# Main_Pannel_ATMega328p_2020-08-23_19-58-.net
KiCad netlist of a schematic drawn in EasyEDA
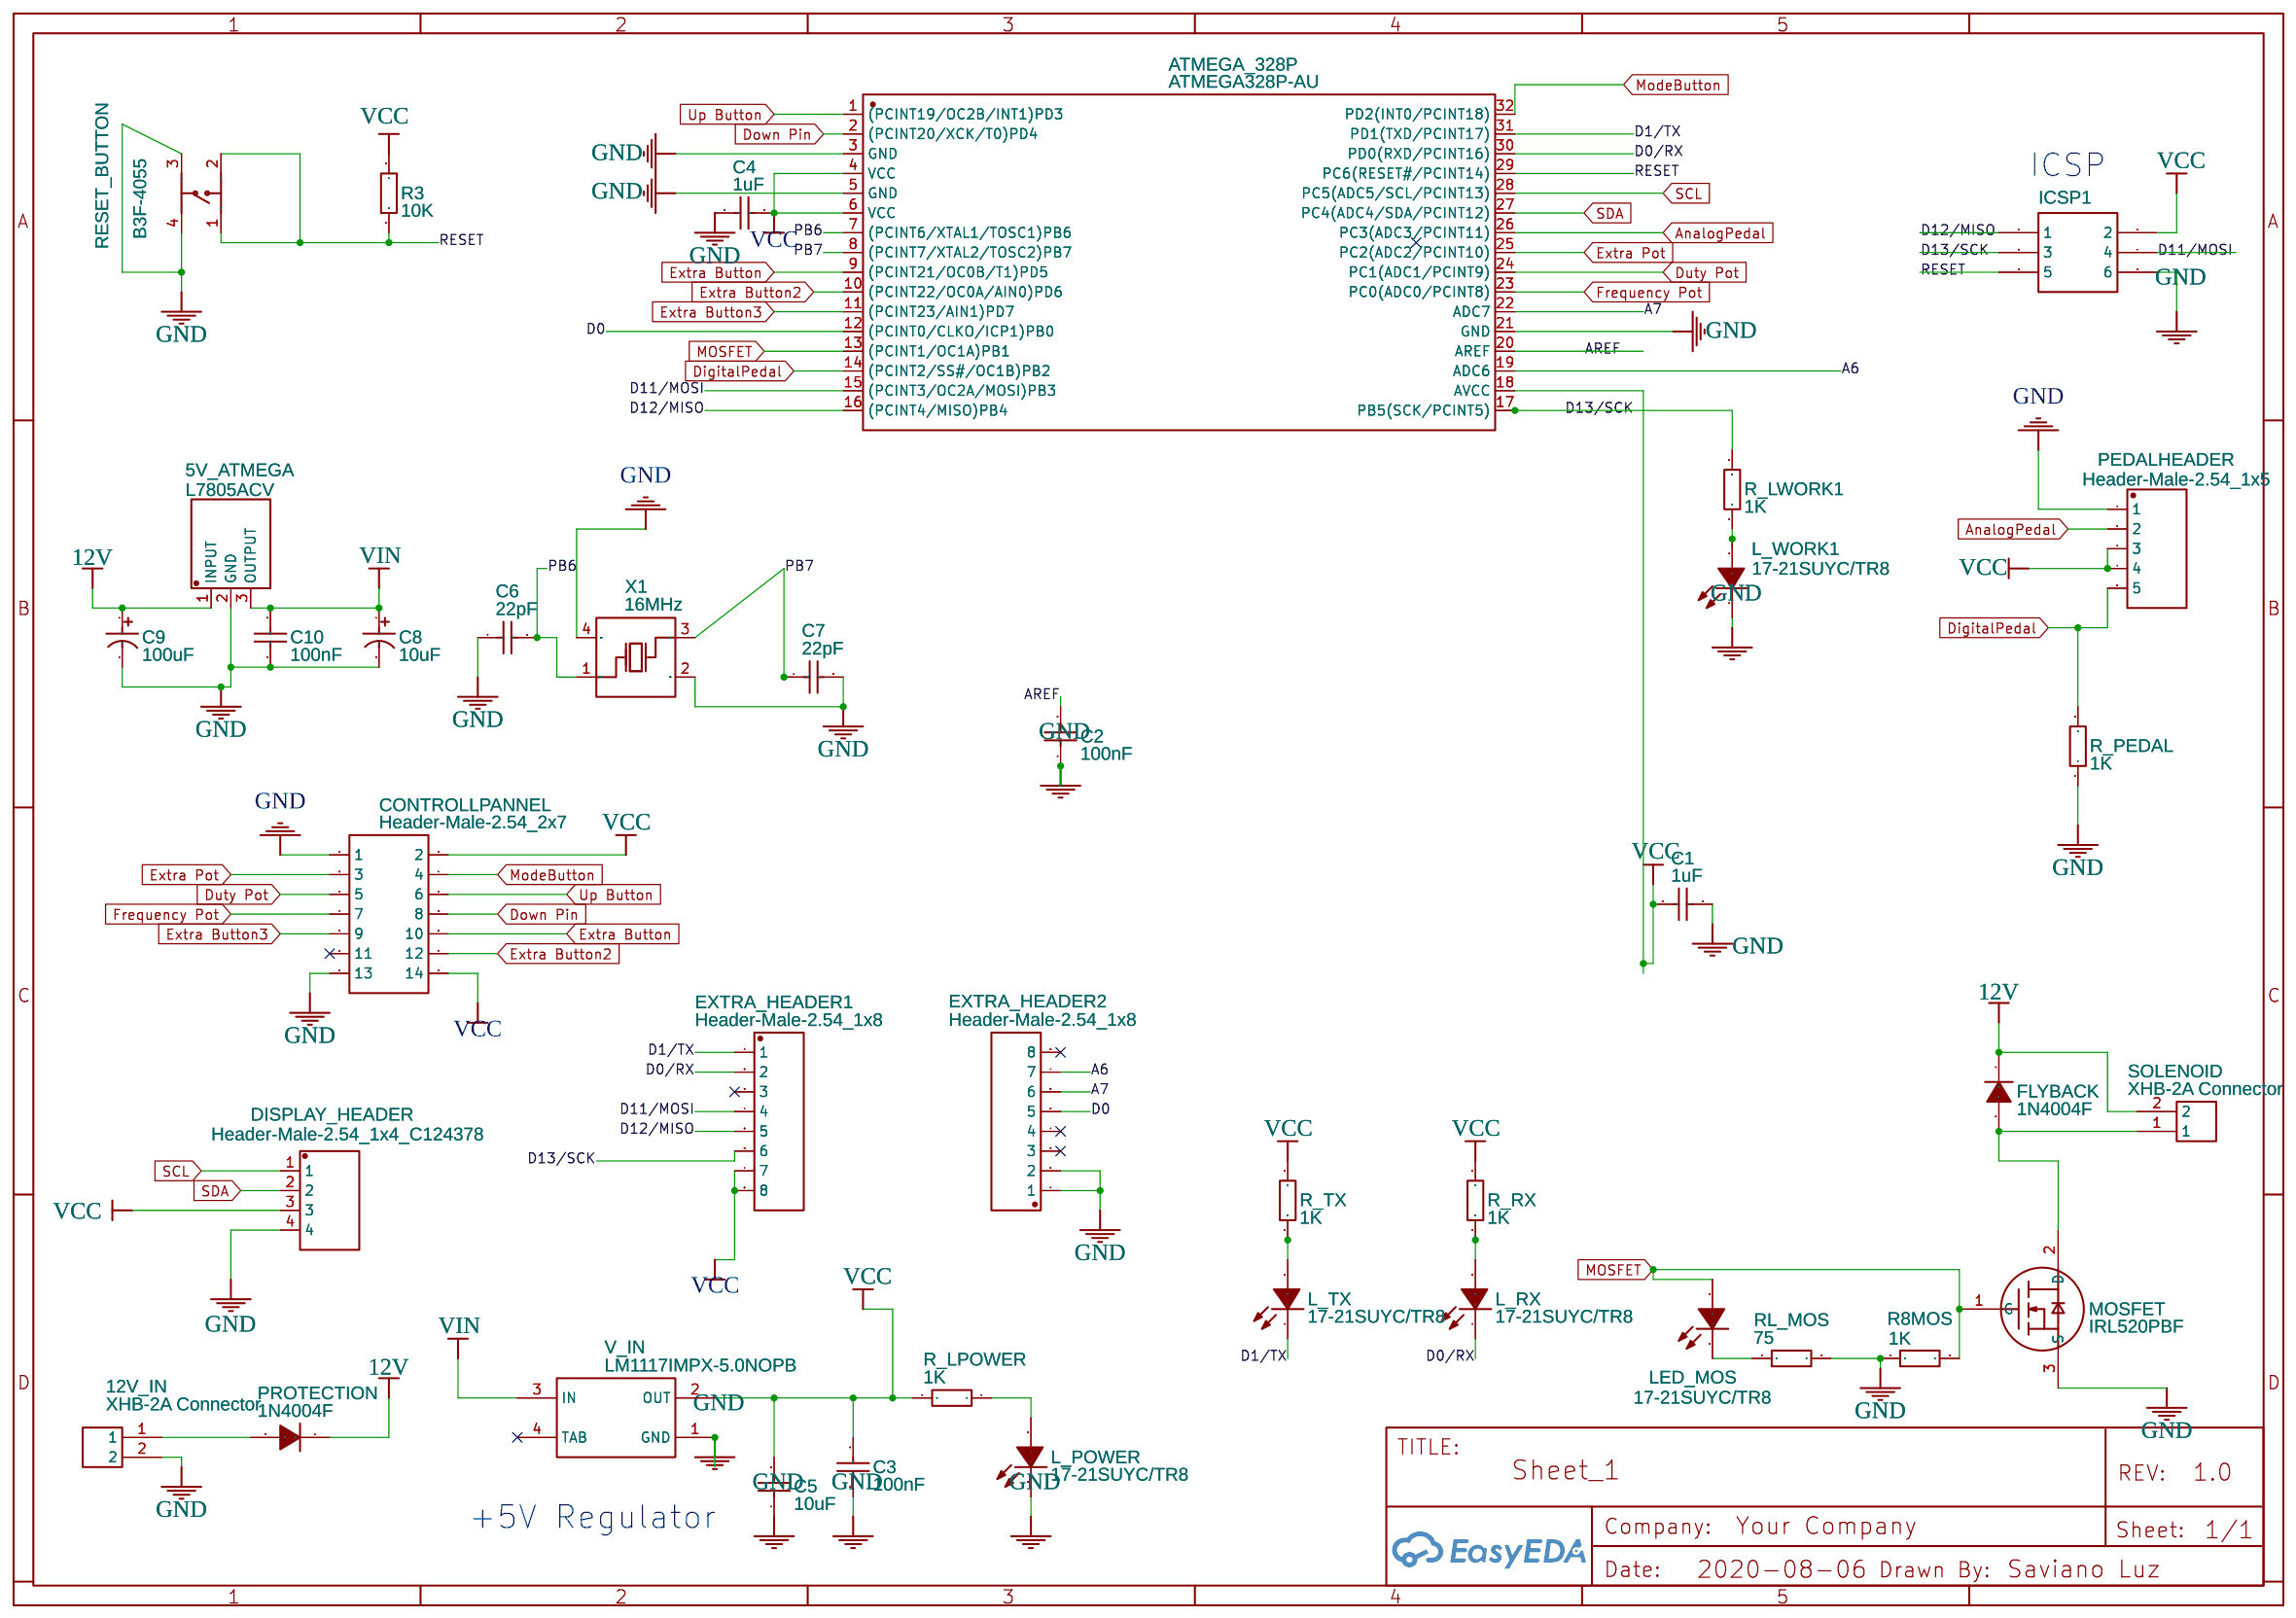
[diagram p0: schematic sheet]

(export (version "E")
  (design (tool "Eeschema 10.0.6"))
  (components
    (comp (ref "5V_ATMEGA")
      (value "L7805ACV")
      (fields (field (name "BOM_Supplier Part") "C192854"))
      (libsource (lib "") (part "L7805ACV"))
    )
    (comp (ref "12V_IN")
      (value "XHB-2A Connector")
      (fields (field (name "BOM_Supplier Part") "C57981"))
      (libsource (lib "") (part "XHB-2A Connector"))
    )
    (comp (ref "ATMEGA_328P")
      (value "ATMEGA328P-AU")
      (fields (field (name "BOM_Supplier Part") "C14877"))
      (libsource (lib "") (part "ATMEGA328P-AU"))
    )
    (comp (ref "C1")
      (value "1uF")
      (fields
        (field (name "BOM_Manufacturer Part") "CL10A105KB8NNNC")
        (field (name "BOM_Supplier Part") "C15849")
      )
      (libsource (lib "") (part "CL10A105KB8NNNC"))
    )
    (comp (ref "C2")
      (value "100nF")
      (fields
        (field (name "BOM_Manufacturer Part") "CL31B104KBCNNNC")
        (field (name "BOM_Supplier Part") "C24497")
      )
      (libsource (lib "") (part "CL31B104KBCNNNC"))
    )
    (comp (ref "C3")
      (value "100nF")
      (fields
        (field (name "BOM_Manufacturer Part") "CL31B104KBCNNNC")
        (field (name "BOM_Supplier Part") "C24497")
      )
      (libsource (lib "") (part "CL31B104KBCNNNC"))
    )
    (comp (ref "C4")
      (value "1uF")
      (fields
        (field (name "BOM_Manufacturer Part") "CL10A105KB8NNNC")
        (field (name "BOM_Supplier Part") "C15849")
      )
      (libsource (lib "") (part "CL10A105KB8NNNC"))
    )
    (comp (ref "C5")
      (value "10uF")
      (fields
        (field (name "BOM_Manufacturer Part") "CL31A106KBHNNNE")
        (field (name "BOM_Supplier Part") "C13585")
      )
      (libsource (lib "") (part "CL31A106KBHNNNE"))
    )
    (comp (ref "C6")
      (value "22pF")
      (fields
        (field (name "BOM_Manufacturer Part") "CL21C220JBANNNC")
        (field (name "BOM_Supplier Part") "C1804")
      )
      (libsource (lib "") (part "CL21C220JBANNNC"))
    )
    (comp (ref "C7")
      (value "22pF")
      (fields
        (field (name "BOM_Manufacturer Part") "CL21C220JBANNNC")
        (field (name "BOM_Supplier Part") "C1804")
      )
      (libsource (lib "") (part "CL21C220JBANNNC"))
    )
    (comp (ref "C8")
      (value "10uF")
      (fields
        (field (name "BOM_Manufacturer Part") "C10uF63V2.5mm5x11mm")
        (field (name "BOM_Supplier Part") "C32455")
      )
      (libsource (lib "") (part "C10uF63V2.5mm5x11mm"))
    )
    (comp (ref "C9")
      (value "100uF")
      (fields
        (field (name "BOM_Manufacturer Part") "10X17 100V100uf")
        (field (name "BOM_Supplier Part") "C3336")
      )
      (libsource (lib "") (part "10X17 100V100uf"))
    )
    (comp (ref "C10")
      (value "100nF")
      (fields
        (field (name "BOM_Manufacturer Part") "CL31B104KBCNNNC")
        (field (name "BOM_Supplier Part") "C24497")
      )
      (libsource (lib "") (part "CL31B104KBCNNNC"))
    )
    (comp (ref "CONTROLLPANNEL")
      (value "Header-Male-2.54_2x7")
      (fields
        (field (name "BOM_Manufacturer Part") "Double row of needle2X7P 2.54mm")
        (field (name "BOM_Supplier Part") "C71397")
      )
      (libsource (lib "") (part "Header-Male-2.54_2x7"))
    )
    (comp (ref "DISPLAY_HEADER")
      (value "Header-Male-2.54_1x4_C124378")
      (fields
        (field (name "BOM_Manufacturer Part") "210S-1*4P L=11.6MMGold-plated black")
        (field (name "BOM_Supplier Part") "C124378")
      )
      (libsource (lib "") (part "Header-Male-2.54_1x4_C124378"))
    )
    (comp (ref "EXTRA_HEADER1")
      (value "Header-Male-2.54_1x8")
      (fields
        (field (name "BOM_Manufacturer Part") "210S-1*8P L=11.6MMGold-plated black")
        (field (name "BOM_Supplier Part") "C124381")
      )
      (libsource (lib "") (part "Header-Male-2.54_1x8"))
    )
    (comp (ref "EXTRA_HEADER2")
      (value "Header-Male-2.54_1x8")
      (fields
        (field (name "BOM_Manufacturer Part") "210S-1*8P L=11.6MMGold-plated black")
        (field (name "BOM_Supplier Part") "C124381")
      )
      (libsource (lib "") (part "Header-Male-2.54_1x8_1"))
    )
    (comp (ref "FLYBACK")
      (value "1N4004F")
      (fields (field (name "BOM_Supplier Part") "C122842"))
      (libsource (lib "") (part "1N4004F"))
    )
    (comp (ref "ICSP1")
      (value "HDR2X3")
      (fields (field (name "BOM_Manufacturer Part") "?"))
      (libsource (lib "") (part "Unknown_1045_-685"))
    )
    (comp (ref "LED_MOS")
      (value "17-21SUYC/TR8")
      (fields (field (name "BOM_Supplier Part") "C2296"))
      (libsource (lib "") (part "17-21SUYC/TR8_1"))
    )
    (comp (ref "L_POWER")
      (value "17-21SUYC/TR8")
      (fields (field (name "BOM_Supplier Part") "C2296"))
      (libsource (lib "") (part "17-21SUYC/TR8_2"))
    )
    (comp (ref "L_RX")
      (value "17-21SUYC/TR8")
      (fields (field (name "BOM_Supplier Part") "C2296"))
      (libsource (lib "") (part "17-21SUYC/TR8_3"))
    )
    (comp (ref "L_TX")
      (value "17-21SUYC/TR8")
      (fields (field (name "BOM_Supplier Part") "C2296"))
      (libsource (lib "") (part "17-21SUYC/TR8"))
    )
    (comp (ref "L_WORK1")
      (value "17-21SUYC/TR8")
      (fields (field (name "BOM_Supplier Part") "C2296"))
      (libsource (lib "") (part "17-21SUYC/TR8_4"))
    )
    (comp (ref "MOSFET")
      (value "IRL520PBF")
      (fields (field (name "BOM_Supplier Part") "C145199"))
      (libsource (lib "") (part "IRL520PBF"))
    )
    (comp (ref "PEDALHEADER")
      (value "Header-Male-2.54_1x5")
      (fields
        (field (name "BOM_Manufacturer Part") "210S-1*5P L=11.6MMGold-plated black")
        (field (name "BOM_Supplier Part") "C124379")
      )
      (libsource (lib "") (part "Header-Male-2.54_1x5"))
    )
    (comp (ref "PROTECTION")
      (value "1N4004F")
      (fields (field (name "BOM_Supplier Part") "C122842"))
      (libsource (lib "") (part "1N4004F_1"))
    )
    (comp (ref "R3")
      (value "10K")
      (fields
        (field (name "BOM_Manufacturer Part") "0805W8F1002T5E")
        (field (name "BOM_Supplier Part") "C17414")
      )
      (libsource (lib "") (part "0805W8F1002T5E"))
    )
    (comp (ref "R8MOS")
      (value "1K")
      (fields
        (field (name "BOM_Manufacturer Part") "1206W4F1001T5E")
        (field (name "BOM_Supplier Part") "C4410")
      )
      (libsource (lib "") (part "1206W4F1001T5E"))
    )
    (comp (ref "RESET_BUTTON")
      (value "B3F-4055")
      (fields (field (name "BOM_Supplier Part") "C84931"))
      (libsource (lib "") (part "B3F-4055"))
    )
    (comp (ref "RL_MOS")
      (value "75")
      (fields
        (field (name "BOM_Manufacturer Part") "0805W8F750JT5E")
        (field (name "BOM_Supplier Part") "C20638")
      )
      (libsource (lib "") (part "0805W8F750JT5E"))
    )
    (comp (ref "R_LPOWER")
      (value "1K")
      (fields
        (field (name "BOM_Manufacturer Part") "0805W8F1001T5E")
        (field (name "BOM_Supplier Part") "C17513")
      )
      (libsource (lib "") (part "0805W8F1001T5E_2"))
    )
    (comp (ref "R_LWORK1")
      (value "1K")
      (fields
        (field (name "BOM_Manufacturer Part") "0805W8F1001T5E")
        (field (name "BOM_Supplier Part") "C17513")
      )
      (libsource (lib "") (part "0805W8F1001T5E_4"))
    )
    (comp (ref "R_PEDAL")
      (value "1K")
      (fields
        (field (name "BOM_Manufacturer Part") "0805W8F1001T5E")
        (field (name "BOM_Supplier Part") "C17513")
      )
      (libsource (lib "") (part "0805W8F1001T5E"))
    )
    (comp (ref "R_RX")
      (value "1K")
      (fields
        (field (name "BOM_Manufacturer Part") "0805W8F1001T5E")
        (field (name "BOM_Supplier Part") "C17513")
      )
      (libsource (lib "") (part "0805W8F1001T5E_1"))
    )
    (comp (ref "R_TX")
      (value "1K")
      (fields
        (field (name "BOM_Manufacturer Part") "0805W8F1001T5E")
        (field (name "BOM_Supplier Part") "C17513")
      )
      (libsource (lib "") (part "0805W8F1001T5E_3"))
    )
    (comp (ref "SOLENOID")
      (value "XHB-2A Connector")
      (fields (field (name "BOM_Supplier Part") "C57981"))
      (libsource (lib "") (part "XHB-2A Connector_1"))
    )
    (comp (ref "V_IN")
      (value "LM1117IMPX-5.0NOPB")
      (fields (field (name "BOM_Manufacturer Part") "?") (field (name "BOM_Supplier Part") "C41202"))
      (libsource (lib "") (part "Unknown_305_-95"))
    )
    (comp (ref "X1")
      (value "16MHz")
      (fields
        (field (name "BOM_Manufacturer Part") "X322516MLB4SI")
        (field (name "BOM_Supplier Part") "C13738")
      )
      (libsource (lib "") (part "X322516MLB4SI"))
    )
  )
  (nets
    (net (code "1") (name "/A6") (class "Default")
      (node (ref "ATMEGA_328P") (pin "19") (pinfunction "ADC6_19") (pintype "unspecified"))
      (node (ref "EXTRA_HEADER2") (pin "7") (pinfunction "7_7") (pintype "unspecified"))
    )
    (net (code "2") (name "/A7") (class "Default")
      (node (ref "ATMEGA_328P") (pin "22") (pinfunction "ADC7_22") (pintype "unspecified"))
      (node (ref "EXTRA_HEADER2") (pin "6") (pinfunction "6_6") (pintype "unspecified"))
    )
    (net (code "3") (name "/AREF") (class "Default")
      (node (ref "ATMEGA_328P") (pin "20") (pinfunction "AREF_20") (pintype "unspecified"))
      (node (ref "C2") (pin "2") (pinfunction "2_2") (pintype "input"))
    )
    (net (code "4") (name "/D0") (class "Default")
      (node (ref "ATMEGA_328P") (pin "12") (pinfunction "(PCINT0/CLKO/ICP1)PB0_12") (pintype "unspecified"))
      (node (ref "EXTRA_HEADER2") (pin "5") (pinfunction "5_5") (pintype "unspecified"))
    )
    (net (code "5") (name "/D0{slash}RX") (class "Default")
      (node (ref "ATMEGA_328P") (pin "30") (pinfunction "PD0(RXD/PCINT16)_30") (pintype "unspecified"))
      (node (ref "EXTRA_HEADER1") (pin "2") (pinfunction "2_2") (pintype "unspecified"))
      (node (ref "L_RX") (pin "1") (pinfunction "-_1") (pintype "unspecified"))
    )
    (net (code "6") (name "/D1{slash}TX") (class "Default")
      (node (ref "ATMEGA_328P") (pin "31") (pinfunction "PD1(TXD/PCINT17)_31") (pintype "unspecified"))
      (node (ref "EXTRA_HEADER1") (pin "1") (pinfunction "1_1") (pintype "unspecified"))
      (node (ref "L_TX") (pin "1") (pinfunction "-_1") (pintype "unspecified"))
    )
    (net (code "7") (name "/D11{slash}MOSI") (class "Default")
      (node (ref "ATMEGA_328P") (pin "15") (pinfunction "(PCINT3/OC2A/MOSI)PB3_15") (pintype "unspecified"))
      (node (ref "EXTRA_HEADER1") (pin "4") (pinfunction "4_4") (pintype "unspecified"))
      (node (ref "ICSP1") (pin "4") (pinfunction "4_4") (pintype "unspecified"))
    )
    (net (code "8") (name "/D12{slash}MISO") (class "Default")
      (node (ref "ATMEGA_328P") (pin "16") (pinfunction "(PCINT4/MISO)PB4_16") (pintype "unspecified"))
      (node (ref "EXTRA_HEADER1") (pin "5") (pinfunction "5_5") (pintype "unspecified"))
      (node (ref "ICSP1") (pin "1") (pinfunction "1_1") (pintype "unspecified"))
    )
    (net (code "9") (name "/D13{slash}SCK") (class "Default")
      (node (ref "ATMEGA_328P") (pin "17") (pinfunction "PB5(SCK/PCINT5)_17") (pintype "unspecified"))
      (node (ref "EXTRA_HEADER1") (pin "6") (pinfunction "6_6") (pintype "unspecified"))
      (node (ref "ICSP1") (pin "3") (pinfunction "3_3") (pintype "unspecified"))
      (node (ref "R_LWORK1") (pin "2") (pinfunction "2_2") (pintype "input"))
    )
    (net (code "10") (name "/PB6") (class "Default")
      (node (ref "ATMEGA_328P") (pin "7") (pinfunction "(PCINT6/XTAL1/TOSC1)PB6_7") (pintype "unspecified"))
      (node (ref "C6") (pin "2") (pinfunction "2_2") (pintype "input"))
      (node (ref "X1") (pin "1") (pinfunction "OSC1_1") (pintype "unspecified"))
    )
    (net (code "11") (name "/PB7") (class "Default")
      (node (ref "ATMEGA_328P") (pin "8") (pinfunction "(PCINT7/XTAL2/TOSC2)PB7_8") (pintype "unspecified"))
      (node (ref "C7") (pin "1") (pinfunction "1_1") (pintype "input"))
      (node (ref "X1") (pin "3") (pinfunction "OSC2_3") (pintype "unspecified"))
    )
    (net (code "12") (name "/RESET") (class "Default")
      (node (ref "ATMEGA_328P") (pin "29") (pinfunction "PC6(RESET#/PCINT14)_29") (pintype "unspecified"))
      (node (ref "ICSP1") (pin "5") (pinfunction "5_5") (pintype "unspecified"))
      (node (ref "R3") (pin "1") (pinfunction "1_1") (pintype "input"))
      (node (ref "RESET_BUTTON") (pin "1") (pinfunction "1_1") (pintype "unspecified"))
      (node (ref "RESET_BUTTON") (pin "2") (pinfunction "2_2") (pintype "unspecified"))
    )
    (net (code "13") (name "12V") (class "Default")
      (node (ref "5V_ATMEGA") (pin "1") (pinfunction "INPUT_1") (pintype "unspecified"))
      (node (ref "C9") (pin "1") (pinfunction "1_1") (pintype "input"))
      (node (ref "FLYBACK") (pin "1") (pinfunction "C_1") (pintype "unspecified"))
      (node (ref "PROTECTION") (pin "1") (pinfunction "C_1") (pintype "unspecified"))
      (node (ref "SOLENOID") (pin "2") (pinfunction "2_2") (pintype "unspecified"))
    )
    (net (code "14") (name "AnalogPedal") (class "Default")
      (node (ref "ATMEGA_328P") (pin "26") (pinfunction "PC3(ADC3/PCINT11)_26") (pintype "unspecified"))
      (node (ref "PEDALHEADER") (pin "2") (pinfunction "2_2") (pintype "unspecified"))
    )
    (net (code "15") (name "DigitalPedal") (class "Default")
      (node (ref "ATMEGA_328P") (pin "14") (pinfunction "(PCINT2/SS#/OC1B)PB2_14") (pintype "unspecified"))
      (node (ref "PEDALHEADER") (pin "5") (pinfunction "5_5") (pintype "unspecified"))
      (node (ref "R_PEDAL") (pin "2") (pinfunction "2_2") (pintype "input"))
    )
    (net (code "16") (name "Down Pin") (class "Default")
      (node (ref "ATMEGA_328P") (pin "2") (pinfunction "(PCINT20/XCK/T0)PD4_2") (pintype "unspecified"))
      (node (ref "CONTROLLPANNEL") (pin "8") (pinfunction "8_8") (pintype "input"))
    )
    (net (code "17") (name "Duty Pot") (class "Default")
      (node (ref "ATMEGA_328P") (pin "24") (pinfunction "PC1(ADC1/PCINT9)_24") (pintype "unspecified"))
      (node (ref "CONTROLLPANNEL") (pin "5") (pinfunction "5_5") (pintype "input"))
    )
    (net (code "18") (name "Extra Button") (class "Default")
      (node (ref "ATMEGA_328P") (pin "9") (pinfunction "(PCINT21/OC0B/T1)PD5_9") (pintype "unspecified"))
      (node (ref "CONTROLLPANNEL") (pin "10") (pinfunction "10_10") (pintype "input"))
    )
    (net (code "19") (name "Extra Button2") (class "Default")
      (node (ref "ATMEGA_328P") (pin "10") (pinfunction "(PCINT22/OC0A/AIN0)PD6_10") (pintype "unspecified"))
      (node (ref "CONTROLLPANNEL") (pin "12") (pinfunction "12_12") (pintype "input"))
    )
    (net (code "20") (name "Extra Button3") (class "Default")
      (node (ref "ATMEGA_328P") (pin "11") (pinfunction "(PCINT23/AIN1)PD7_11") (pintype "unspecified"))
      (node (ref "CONTROLLPANNEL") (pin "9") (pinfunction "9_9") (pintype "input"))
    )
    (net (code "21") (name "Extra Pot") (class "Default")
      (node (ref "ATMEGA_328P") (pin "25") (pinfunction "PC2(ADC2/PCINT10)_25") (pintype "unspecified"))
      (node (ref "CONTROLLPANNEL") (pin "3") (pinfunction "3_3") (pintype "input"))
    )
    (net (code "22") (name "Frequency Pot") (class "Default")
      (node (ref "ATMEGA_328P") (pin "23") (pinfunction "PC0(ADC0/PCINT8)_23") (pintype "unspecified"))
      (node (ref "CONTROLLPANNEL") (pin "7") (pinfunction "7_7") (pintype "input"))
    )
    (net (code "23") (name "GND") (class "Default")
      (node (ref "12V_IN") (pin "2") (pinfunction "2_2") (pintype "unspecified"))
      (node (ref "5V_ATMEGA") (pin "2") (pinfunction "GND_2") (pintype "unspecified"))
      (node (ref "ATMEGA_328P") (pin "21") (pinfunction "GND_21") (pintype "unspecified"))
      (node (ref "ATMEGA_328P") (pin "3") (pinfunction "GND_3") (pintype "unspecified"))
      (node (ref "ATMEGA_328P") (pin "5") (pinfunction "GND_5") (pintype "unspecified"))
      (node (ref "C1") (pin "2") (pinfunction "2_2") (pintype "input"))
      (node (ref "C10") (pin "1") (pinfunction "1_1") (pintype "input"))
      (node (ref "C2") (pin "1") (pinfunction "1_1") (pintype "input"))
      (node (ref "C3") (pin "1") (pinfunction "1_1") (pintype "input"))
      (node (ref "C4") (pin "1") (pinfunction "1_1") (pintype "input"))
      (node (ref "C5") (pin "1") (pinfunction "1_1") (pintype "input"))
      (node (ref "C6") (pin "1") (pinfunction "1_1") (pintype "input"))
      (node (ref "C7") (pin "2") (pinfunction "2_2") (pintype "input"))
      (node (ref "C8") (pin "2") (pinfunction "2_2") (pintype "input"))
      (node (ref "C9") (pin "2") (pinfunction "2_2") (pintype "input"))
      (node (ref "CONTROLLPANNEL") (pin "1") (pinfunction "1_1") (pintype "input"))
      (node (ref "CONTROLLPANNEL") (pin "13") (pinfunction "13_13") (pintype "input"))
      (node (ref "DISPLAY_HEADER") (pin "4") (pinfunction "4_4") (pintype "unspecified"))
      (node (ref "EXTRA_HEADER2") (pin "1") (pinfunction "1_1") (pintype "unspecified"))
      (node (ref "EXTRA_HEADER2") (pin "2") (pinfunction "2_2") (pintype "unspecified"))
      (node (ref "ICSP1") (pin "6") (pinfunction "6_6") (pintype "unspecified"))
      (node (ref "L_POWER") (pin "1") (pinfunction "-_1") (pintype "unspecified"))
      (node (ref "L_WORK1") (pin "1") (pinfunction "-_1") (pintype "unspecified"))
      (node (ref "MOSFET") (pin "3") (pinfunction "S_3") (pintype "unspecified"))
      (node (ref "PEDALHEADER") (pin "1") (pinfunction "1_1") (pintype "unspecified"))
      (node (ref "R8MOS") (pin "1") (pinfunction "1_1") (pintype "input"))
      (node (ref "RESET_BUTTON") (pin "3") (pinfunction "3_3") (pintype "unspecified"))
      (node (ref "RESET_BUTTON") (pin "4") (pinfunction "4_4") (pintype "unspecified"))
      (node (ref "RL_MOS") (pin "2") (pinfunction "2_2") (pintype "input"))
      (node (ref "R_PEDAL") (pin "1") (pinfunction "1_1") (pintype "input"))
      (node (ref "V_IN") (pin "1") (pinfunction "GND_1") (pintype "passive"))
      (node (ref "X1") (pin "2") (pinfunction "GND_2") (pintype "unspecified"))
      (node (ref "X1") (pin "4") (pinfunction "GND_4") (pintype "unspecified"))
    )
    (net (code "24") (name "MOSFET") (class "Default")
      (node (ref "ATMEGA_328P") (pin "13") (pinfunction "(PCINT1/OC1A)PB1_13") (pintype "unspecified"))
      (node (ref "LED_MOS") (pin "2") (pinfunction "+_2") (pintype "unspecified"))
      (node (ref "MOSFET") (pin "1") (pinfunction "G_1") (pintype "unspecified"))
      (node (ref "R8MOS") (pin "2") (pinfunction "2_2") (pintype "input"))
    )
    (net (code "25") (name "ModeButton") (class "Default")
      (node (ref "ATMEGA_328P") (pin "32") (pinfunction "PD2(INT0/PCINT18)_32") (pintype "unspecified"))
      (node (ref "CONTROLLPANNEL") (pin "4") (pinfunction "4_4") (pintype "input"))
    )
    (net (code "26") (name "Net-(FLYBACK-A)") (class "Default")
      (node (ref "FLYBACK") (pin "2") (pinfunction "A_2") (pintype "unspecified"))
      (node (ref "MOSFET") (pin "2") (pinfunction "D_2") (pintype "unspecified"))
      (node (ref "SOLENOID") (pin "1") (pinfunction "1_1") (pintype "unspecified"))
    )
    (net (code "27") (name "Net-(LED_MOS--)") (class "Default")
      (node (ref "LED_MOS") (pin "1") (pinfunction "-_1") (pintype "unspecified"))
      (node (ref "RL_MOS") (pin "1") (pinfunction "1_1") (pintype "input"))
    )
    (net (code "28") (name "Net-(L_POWER-+)") (class "Default")
      (node (ref "L_POWER") (pin "2") (pinfunction "+_2") (pintype "unspecified"))
      (node (ref "R_LPOWER") (pin "1") (pinfunction "1_1") (pintype "input"))
    )
    (net (code "29") (name "Net-(L_RX-+)") (class "Default")
      (node (ref "L_RX") (pin "2") (pinfunction "+_2") (pintype "unspecified"))
      (node (ref "R_RX") (pin "1") (pinfunction "1_1") (pintype "input"))
    )
    (net (code "30") (name "Net-(L_TX-+)") (class "Default")
      (node (ref "L_TX") (pin "2") (pinfunction "+_2") (pintype "unspecified"))
      (node (ref "R_TX") (pin "1") (pinfunction "1_1") (pintype "input"))
    )
    (net (code "31") (name "Net-(L_WORK1-+)") (class "Default")
      (node (ref "L_WORK1") (pin "2") (pinfunction "+_2") (pintype "unspecified"))
      (node (ref "R_LWORK1") (pin "1") (pinfunction "1_1") (pintype "input"))
    )
    (net (code "32") (name "Net-(PROTECTION-A)") (class "Default")
      (node (ref "12V_IN") (pin "1") (pinfunction "1_1") (pintype "unspecified"))
      (node (ref "PROTECTION") (pin "2") (pinfunction "A_2") (pintype "unspecified"))
    )
    (net (code "33") (name "SCL") (class "Default")
      (node (ref "ATMEGA_328P") (pin "28") (pinfunction "PC5(ADC5/SCL/PCINT13)_28") (pintype "unspecified"))
      (node (ref "DISPLAY_HEADER") (pin "1") (pinfunction "1_1") (pintype "unspecified"))
    )
    (net (code "34") (name "SDA") (class "Default")
      (node (ref "ATMEGA_328P") (pin "27") (pinfunction "PC4(ADC4/SDA/PCINT12)_27") (pintype "unspecified"))
      (node (ref "DISPLAY_HEADER") (pin "2") (pinfunction "2_2") (pintype "unspecified"))
    )
    (net (code "35") (name "Up Button") (class "Default")
      (node (ref "ATMEGA_328P") (pin "1") (pinfunction "(PCINT19/OC2B/INT1)PD3_1") (pintype "unspecified"))
      (node (ref "CONTROLLPANNEL") (pin "6") (pinfunction "6_6") (pintype "input"))
    )
    (net (code "36") (name "VCC") (class "Default")
      (node (ref "ATMEGA_328P") (pin "18") (pinfunction "AVCC_18") (pintype "unspecified"))
      (node (ref "ATMEGA_328P") (pin "4") (pinfunction "VCC_4") (pintype "unspecified"))
      (node (ref "ATMEGA_328P") (pin "6") (pinfunction "VCC_6") (pintype "unspecified"))
      (node (ref "C1") (pin "1") (pinfunction "1_1") (pintype "input"))
      (node (ref "C3") (pin "2") (pinfunction "2_2") (pintype "input"))
      (node (ref "C4") (pin "2") (pinfunction "2_2") (pintype "input"))
      (node (ref "C5") (pin "2") (pinfunction "2_2") (pintype "input"))
      (node (ref "CONTROLLPANNEL") (pin "14") (pinfunction "14_14") (pintype "input"))
      (node (ref "CONTROLLPANNEL") (pin "2") (pinfunction "2_2") (pintype "input"))
      (node (ref "DISPLAY_HEADER") (pin "3") (pinfunction "3_3") (pintype "unspecified"))
      (node (ref "EXTRA_HEADER1") (pin "7") (pinfunction "7_7") (pintype "unspecified"))
      (node (ref "EXTRA_HEADER1") (pin "8") (pinfunction "8_8") (pintype "unspecified"))
      (node (ref "ICSP1") (pin "2") (pinfunction "2_2") (pintype "unspecified"))
      (node (ref "PEDALHEADER") (pin "3") (pinfunction "3_3") (pintype "unspecified"))
      (node (ref "PEDALHEADER") (pin "4") (pinfunction "4_4") (pintype "unspecified"))
      (node (ref "R3") (pin "2") (pinfunction "2_2") (pintype "input"))
      (node (ref "R_LPOWER") (pin "2") (pinfunction "2_2") (pintype "input"))
      (node (ref "R_RX") (pin "2") (pinfunction "2_2") (pintype "input"))
      (node (ref "R_TX") (pin "2") (pinfunction "2_2") (pintype "input"))
      (node (ref "V_IN") (pin "2") (pinfunction "OUT_2") (pintype "passive"))
    )
    (net (code "37") (name "VIN") (class "Default")
      (node (ref "5V_ATMEGA") (pin "3") (pinfunction "OUTPUT_3") (pintype "unspecified"))
      (node (ref "C10") (pin "2") (pinfunction "2_2") (pintype "input"))
      (node (ref "C8") (pin "1") (pinfunction "1_1") (pintype "input"))
      (node (ref "V_IN") (pin "3") (pinfunction "IN_3") (pintype "passive"))
    )
    (net (code "38") (name "unconnected-(CONTROLLPANNEL-Pad11)") (class "Default")
      (node (ref "CONTROLLPANNEL") (pin "11") (pinfunction "11_11") (pintype "input+no_connect"))
    )
    (net (code "39") (name "unconnected-(EXTRA_HEADER1-Pad3)") (class "Default")
      (node (ref "EXTRA_HEADER1") (pin "3") (pinfunction "3_3") (pintype "unspecified+no_connect"))
    )
    (net (code "40") (name "unconnected-(EXTRA_HEADER2-Pad3)") (class "Default")
      (node (ref "EXTRA_HEADER2") (pin "3") (pinfunction "3_3") (pintype "unspecified+no_connect"))
    )
    (net (code "41") (name "unconnected-(EXTRA_HEADER2-Pad4)") (class "Default")
      (node (ref "EXTRA_HEADER2") (pin "4") (pinfunction "4_4") (pintype "unspecified+no_connect"))
    )
    (net (code "42") (name "unconnected-(EXTRA_HEADER2-Pad8)") (class "Default")
      (node (ref "EXTRA_HEADER2") (pin "8") (pinfunction "8_8") (pintype "unspecified+no_connect"))
    )
    (net (code "43") (name "unconnected-(V_IN-TAB-Pad4)") (class "Default")
      (node (ref "V_IN") (pin "4") (pinfunction "TAB_4") (pintype "passive+no_connect"))
    )
  )
)
